# 05_LMS7002M_RF.net
KiCad netlist of a schematic drawn in Altium Designer
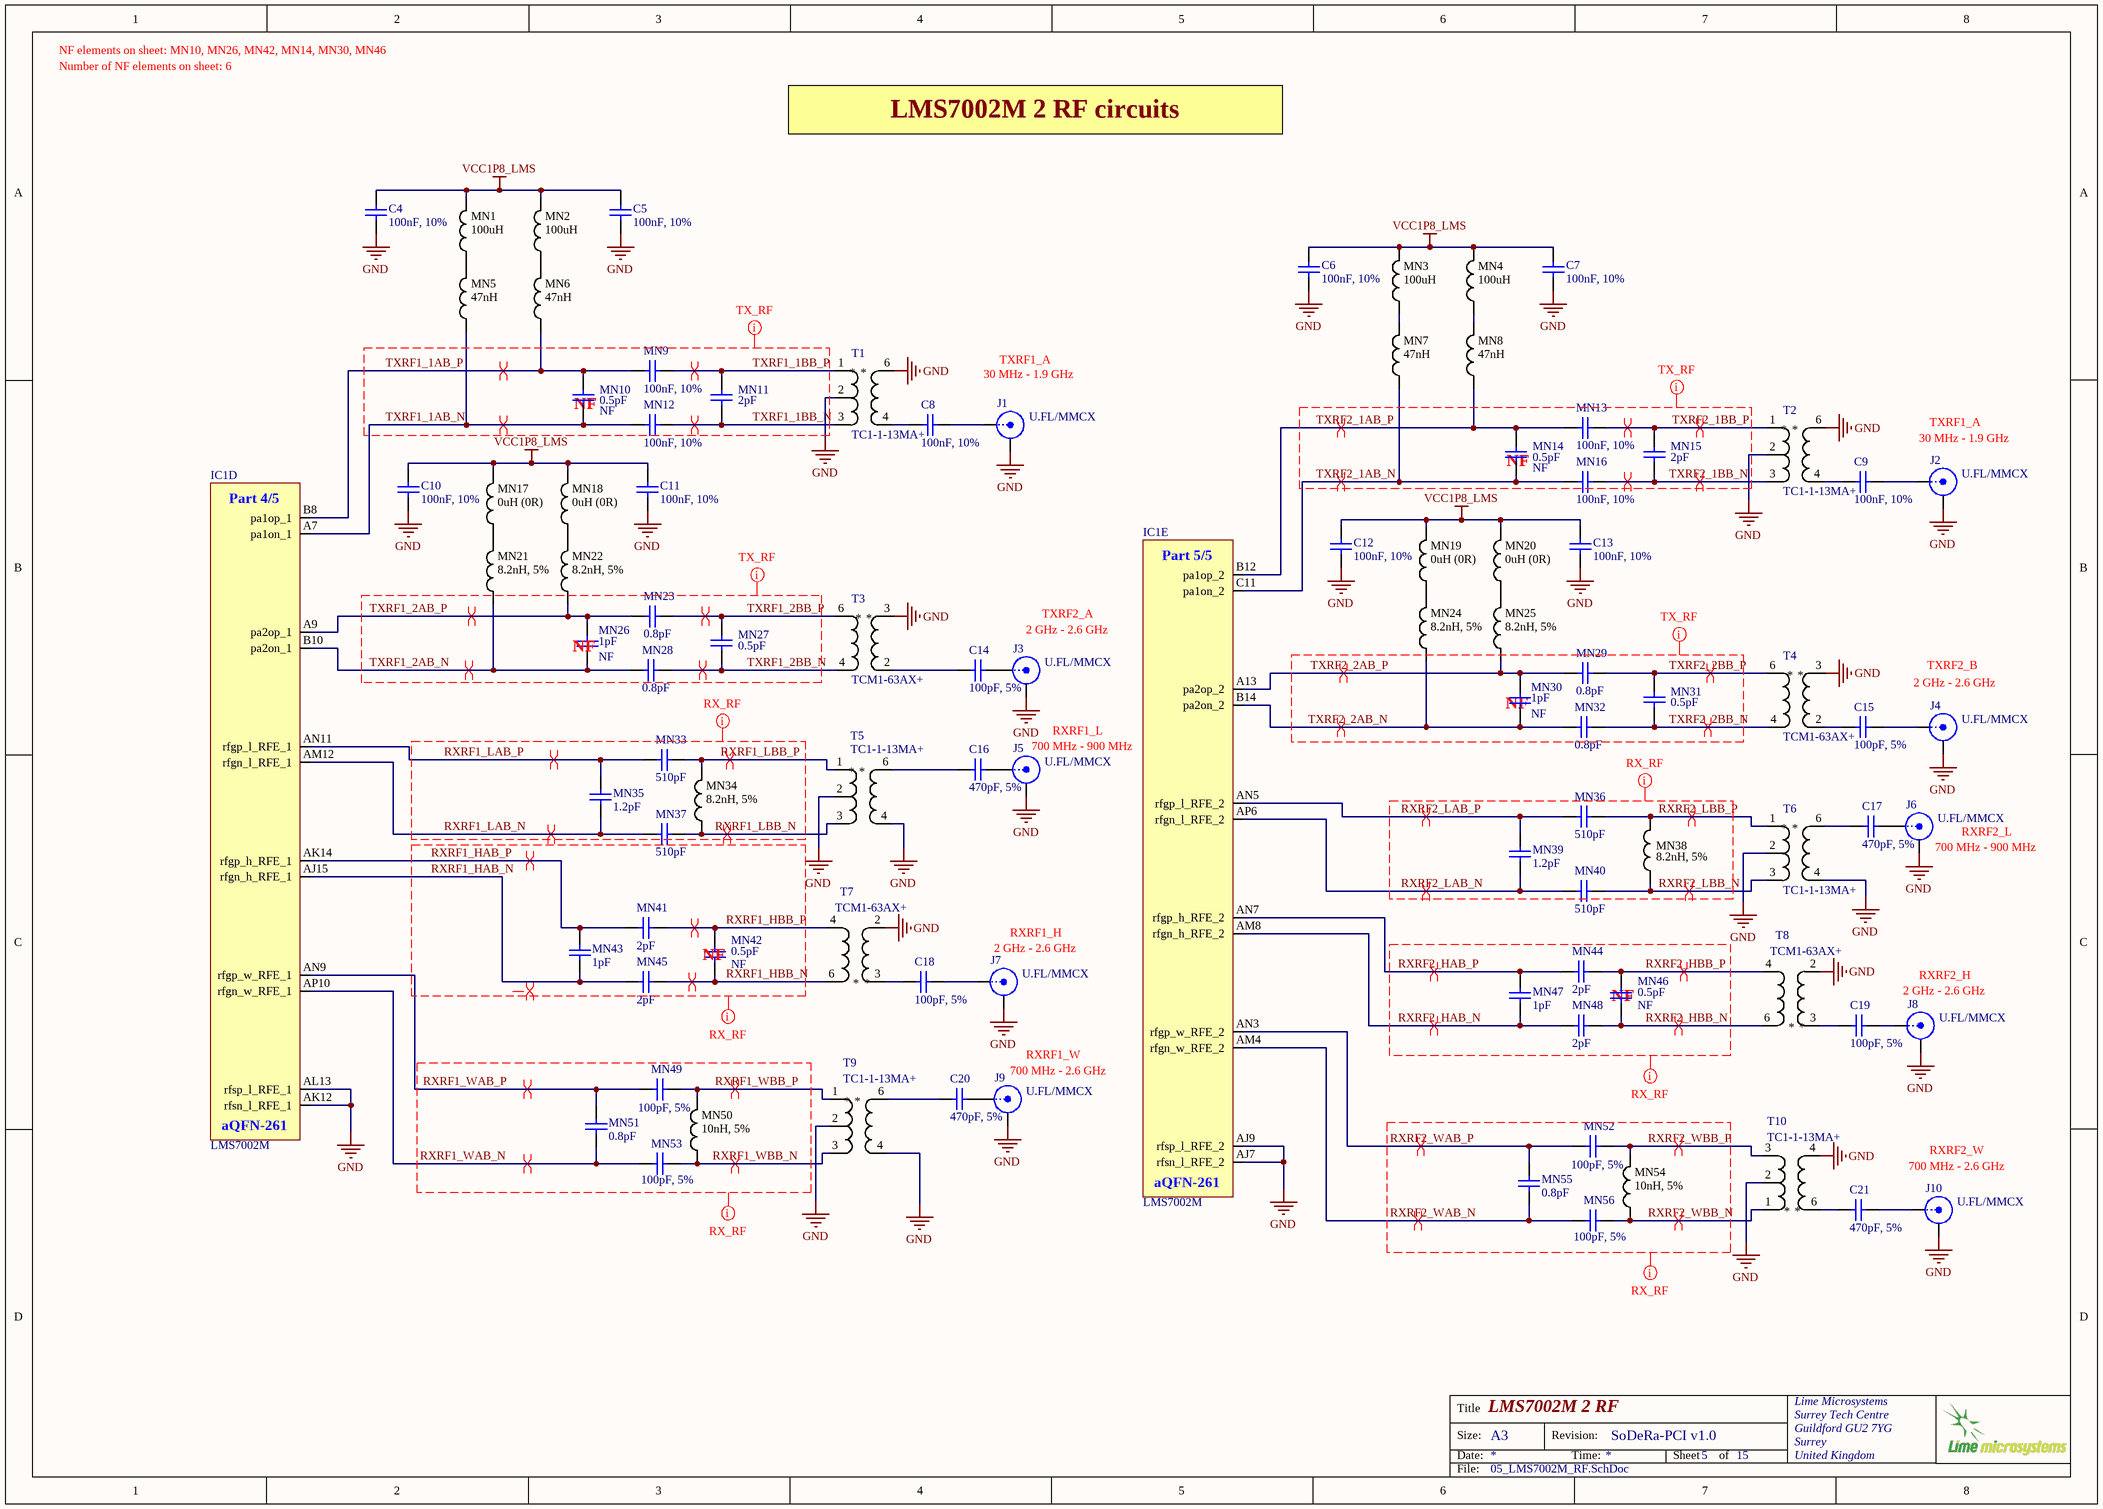
[diagram p0: 05_LMS7002M_RF.SchDoc]

(export (version "E")
  (design (tool "Eeschema 10.0.6"))
  (components
    (comp (ref "C4")
      (value "100nF, 10%")
      (footprint "LimeMicroAltiumLib_pcbLib:CAP0402")
      (fields
        (field (name "MANUFACTURER") "Murata Electronics")
        (field (name "TOLERANCE") "10 %")
        (field (name "MANUFACTURER PART NUMBER") "GRM155R71C104KA88D")
      )
      (libsource (lib "LimeMicroAltiumLib_schLib") (part "Cap_0402"))
    )
    (comp (ref "C5")
      (value "100nF, 10%")
      (footprint "LimeMicroAltiumLib_pcbLib:CAP0402")
      (fields
        (field (name "MANUFACTURER") "Murata Electronics")
        (field (name "TOLERANCE") "10 %")
        (field (name "MANUFACTURER PART NUMBER") "GRM155R71C104KA88D")
      )
      (libsource (lib "LimeMicroAltiumLib_schLib") (part "Cap_0402"))
    )
    (comp (ref "C6")
      (value "100nF, 10%")
      (footprint "LimeMicroAltiumLib_pcbLib:CAP0402")
      (fields
        (field (name "MANUFACTURER") "Murata Electronics")
        (field (name "TOLERANCE") "10 %")
        (field (name "MANUFACTURER PART NUMBER") "GRM155R71C104KA88D")
      )
      (libsource (lib "LimeMicroAltiumLib_schLib") (part "Cap_0402"))
    )
    (comp (ref "C7")
      (value "100nF, 10%")
      (footprint "LimeMicroAltiumLib_pcbLib:CAP0402")
      (fields
        (field (name "MANUFACTURER") "Murata Electronics")
        (field (name "TOLERANCE") "10 %")
        (field (name "MANUFACTURER PART NUMBER") "GRM155R71C104KA88D")
      )
      (libsource (lib "LimeMicroAltiumLib_schLib") (part "Cap_0402"))
    )
    (comp (ref "C8")
      (value "100nF, 10%")
      (footprint "LimeMicroAltiumLib_pcbLib:CAP0402")
      (fields
        (field (name "MANUFACTURER") "Murata Electronics")
        (field (name "TOLERANCE") "10 %")
        (field (name "MANUFACTURER PART NUMBER") "GRM155R71C104KA88D")
      )
      (libsource (lib "LimeMicroAltiumLib_schLib") (part "Cap_0402"))
    )
    (comp (ref "C9")
      (value "100nF, 10%")
      (footprint "LimeMicroAltiumLib_pcbLib:CAP0402")
      (fields
        (field (name "MANUFACTURER") "Murata Electronics")
        (field (name "TOLERANCE") "10 %")
        (field (name "MANUFACTURER PART NUMBER") "GRM155R71C104KA88D")
      )
      (libsource (lib "LimeMicroAltiumLib_schLib") (part "Cap_0402"))
    )
    (comp (ref "C10")
      (value "100nF, 10%")
      (footprint "LimeMicroAltiumLib_pcbLib:CAP0402")
      (fields
        (field (name "MANUFACTURER") "Murata Electronics")
        (field (name "TOLERANCE") "10 %")
        (field (name "MANUFACTURER PART NUMBER") "GRM155R71C104KA88D")
      )
      (libsource (lib "LimeMicroAltiumLib_schLib") (part "Cap_0402"))
    )
    (comp (ref "C11")
      (value "100nF, 10%")
      (footprint "LimeMicroAltiumLib_pcbLib:CAP0402")
      (fields
        (field (name "MANUFACTURER") "Murata Electronics")
        (field (name "TOLERANCE") "10 %")
        (field (name "MANUFACTURER PART NUMBER") "GRM155R71C104KA88D")
      )
      (libsource (lib "LimeMicroAltiumLib_schLib") (part "Cap_0402"))
    )
    (comp (ref "C12")
      (value "100nF, 10%")
      (footprint "LimeMicroAltiumLib_pcbLib:CAP0402")
      (fields
        (field (name "MANUFACTURER") "Murata Electronics")
        (field (name "TOLERANCE") "10 %")
        (field (name "MANUFACTURER PART NUMBER") "GRM155R71C104KA88D")
      )
      (libsource (lib "LimeMicroAltiumLib_schLib") (part "Cap_0402"))
    )
    (comp (ref "C13")
      (value "100nF, 10%")
      (footprint "LimeMicroAltiumLib_pcbLib:CAP0402")
      (fields
        (field (name "MANUFACTURER") "Murata Electronics")
        (field (name "TOLERANCE") "10 %")
        (field (name "MANUFACTURER PART NUMBER") "GRM155R71C104KA88D")
      )
      (libsource (lib "LimeMicroAltiumLib_schLib") (part "Cap_0402"))
    )
    (comp (ref "C14")
      (value "100pF, 5%")
      (footprint "LimeMicroAltiumLib_pcbLib:CAP0402")
      (fields (field (name "TOLERANCE") "±5%") (field (name "MANUFACTURER") "Yageo"))
      (libsource (lib "LimeMicroAltiumLib_schLib") (part "Cap_0402"))
    )
    (comp (ref "C15")
      (value "100pF, 5%")
      (footprint "LimeMicroAltiumLib_pcbLib:CAP0402")
      (fields (field (name "TOLERANCE") "±5%") (field (name "MANUFACTURER") "Yageo"))
      (libsource (lib "LimeMicroAltiumLib_schLib") (part "Cap_0402"))
    )
    (comp (ref "C16")
      (value "470pF, 5%")
      (footprint "LimeMicroAltiumLib_pcbLib:CAP0402")
      (fields
        (field (name "MANUFACTURER PART NUMBER") "C1005C0G1H471J050BA")
        (field (name "TOLERANCE") "±5%")
        (field (name "MANUFACTURER") "TDK Corporation")
      )
      (libsource (lib "LimeMicroAltiumLib_schLib") (part "Cap_0402"))
    )
    (comp (ref "C17")
      (value "470pF, 5%")
      (footprint "LimeMicroAltiumLib_pcbLib:CAP0402")
      (fields
        (field (name "MANUFACTURER PART NUMBER") "C1005C0G1H471J050BA")
        (field (name "TOLERANCE") "±5%")
        (field (name "MANUFACTURER") "TDK Corporation")
      )
      (libsource (lib "LimeMicroAltiumLib_schLib") (part "Cap_0402"))
    )
    (comp (ref "C18")
      (value "100pF, 5%")
      (footprint "LimeMicroAltiumLib_pcbLib:CAP0402")
      (fields (field (name "TOLERANCE") "±5%") (field (name "MANUFACTURER") "Yageo"))
      (libsource (lib "LimeMicroAltiumLib_schLib") (part "Cap_0402"))
    )
    (comp (ref "C19")
      (value "100pF, 5%")
      (footprint "LimeMicroAltiumLib_pcbLib:CAP0402")
      (fields (field (name "TOLERANCE") "±5%") (field (name "MANUFACTURER") "Yageo"))
      (libsource (lib "LimeMicroAltiumLib_schLib") (part "Cap_0402"))
    )
    (comp (ref "C20")
      (value "470pF, 5%")
      (footprint "LimeMicroAltiumLib_pcbLib:CAP0402")
      (fields
        (field (name "MANUFACTURER PART NUMBER") "C1005C0G1H471J050BA")
        (field (name "TOLERANCE") "±5%")
        (field (name "MANUFACTURER") "TDK Corporation")
      )
      (libsource (lib "LimeMicroAltiumLib_schLib") (part "Cap_0402"))
    )
    (comp (ref "C21")
      (value "470pF, 5%")
      (footprint "LimeMicroAltiumLib_pcbLib:CAP0402")
      (fields
        (field (name "MANUFACTURER PART NUMBER") "C1005C0G1H471J050BA")
        (field (name "TOLERANCE") "±5%")
        (field (name "MANUFACTURER") "TDK Corporation")
      )
      (libsource (lib "LimeMicroAltiumLib_schLib") (part "Cap_0402"))
    )
    (comp (ref "IC1")
      (value "LMS7002M")
      (footprint "LimeMicroAltiumLib_pcbLib:LMS7002M")
      (libsource (lib "LimeMicroAltiumLib_schLib") (part "LMS7002M"))
    )
    (comp (ref "J1")
      (value "U.FL/MMCX")
      (footprint "LimeMicroAltiumLib_pcbLib:MMCX_UFL_conn_u")
      (description "CONN UMC RCPT STR 50 OHM SMD")
      (fields (field (name "MANUFACTURER") "Molex, LLC"))
      (libsource (lib "LimeMicroAltiumLib_schLib") (part "RF_IF_connector"))
    )
    (comp (ref "J2")
      (value "U.FL/MMCX")
      (footprint "LimeMicroAltiumLib_pcbLib:MMCX_UFL_conn_u")
      (description "CONN UMC RCPT STR 50 OHM SMD")
      (fields (field (name "MANUFACTURER") "Molex, LLC"))
      (libsource (lib "LimeMicroAltiumLib_schLib") (part "RF_IF_connector"))
    )
    (comp (ref "J3")
      (value "U.FL/MMCX")
      (footprint "LimeMicroAltiumLib_pcbLib:MMCX_UFL_conn_u")
      (description "CONN UMC RCPT STR 50 OHM SMD")
      (fields (field (name "MANUFACTURER") "Molex, LLC"))
      (libsource (lib "LimeMicroAltiumLib_schLib") (part "RF_IF_connector"))
    )
    (comp (ref "J4")
      (value "U.FL/MMCX")
      (footprint "LimeMicroAltiumLib_pcbLib:MMCX_UFL_conn_u")
      (description "CONN UMC RCPT STR 50 OHM SMD")
      (fields (field (name "MANUFACTURER") "Molex, LLC"))
      (libsource (lib "LimeMicroAltiumLib_schLib") (part "RF_IF_connector"))
    )
    (comp (ref "J5")
      (value "U.FL/MMCX")
      (footprint "LimeMicroAltiumLib_pcbLib:MMCX_UFL_conn_u")
      (description "CONN UMC RCPT STR 50 OHM SMD")
      (fields (field (name "MANUFACTURER") "Molex, LLC"))
      (libsource (lib "LimeMicroAltiumLib_schLib") (part "RF_IF_connector"))
    )
    (comp (ref "J6")
      (value "U.FL/MMCX")
      (footprint "LimeMicroAltiumLib_pcbLib:MMCX_UFL_conn_u")
      (description "CONN UMC RCPT STR 50 OHM SMD")
      (fields (field (name "MANUFACTURER") "Molex, LLC"))
      (libsource (lib "LimeMicroAltiumLib_schLib") (part "RF_IF_connector"))
    )
    (comp (ref "J7")
      (value "U.FL/MMCX")
      (footprint "LimeMicroAltiumLib_pcbLib:MMCX_UFL_conn_u")
      (description "CONN UMC RCPT STR 50 OHM SMD")
      (fields (field (name "MANUFACTURER") "Molex, LLC"))
      (libsource (lib "LimeMicroAltiumLib_schLib") (part "RF_IF_connector"))
    )
    (comp (ref "J8")
      (value "U.FL/MMCX")
      (footprint "LimeMicroAltiumLib_pcbLib:MMCX_UFL_conn_u")
      (description "CONN UMC RCPT STR 50 OHM SMD")
      (fields (field (name "MANUFACTURER") "Molex, LLC"))
      (libsource (lib "LimeMicroAltiumLib_schLib") (part "RF_IF_connector"))
    )
    (comp (ref "J9")
      (value "U.FL/MMCX")
      (footprint "LimeMicroAltiumLib_pcbLib:MMCX_UFL_conn_u")
      (description "CONN UMC RCPT STR 50 OHM SMD")
      (fields (field (name "MANUFACTURER") "Molex, LLC"))
      (libsource (lib "LimeMicroAltiumLib_schLib") (part "RF_IF_connector"))
    )
    (comp (ref "J10")
      (value "U.FL/MMCX")
      (footprint "LimeMicroAltiumLib_pcbLib:MMCX_UFL_conn_u")
      (description "CONN UMC RCPT STR 50 OHM SMD")
      (fields (field (name "MANUFACTURER") "Molex, LLC"))
      (libsource (lib "LimeMicroAltiumLib_schLib") (part "RF_IF_connector"))
    )
    (comp (ref "MN1")
      (value "100uH")
      (footprint "LimeMicroAltiumLib_pcbLib:RES0805")
      (fields
        (field (name "TOLERANCE") "±10%")
        (field (name "MANUFACTURER") "TDK Corporation")
        (field (name "MANUFACTURER PART NUMBER") "MLF2012C101KT000")
      )
      (libsource (lib "LimeMicroAltiumLib_schLib") (part "Inductor_0603"))
    )
    (comp (ref "MN2")
      (value "100uH")
      (footprint "LimeMicroAltiumLib_pcbLib:RES0805")
      (fields
        (field (name "TOLERANCE") "±10%")
        (field (name "MANUFACTURER") "TDK Corporation")
        (field (name "MANUFACTURER PART NUMBER") "MLF2012C101KT000")
      )
      (libsource (lib "LimeMicroAltiumLib_schLib") (part "Inductor_0603"))
    )
    (comp (ref "MN3")
      (value "100uH")
      (footprint "LimeMicroAltiumLib_pcbLib:RES0805")
      (fields
        (field (name "TOLERANCE") "±10%")
        (field (name "MANUFACTURER") "TDK Corporation")
        (field (name "MANUFACTURER PART NUMBER") "MLF2012C101KT000")
      )
      (libsource (lib "LimeMicroAltiumLib_schLib") (part "Inductor_0603"))
    )
    (comp (ref "MN4")
      (value "100uH")
      (footprint "LimeMicroAltiumLib_pcbLib:RES0805")
      (fields
        (field (name "TOLERANCE") "±10%")
        (field (name "MANUFACTURER") "TDK Corporation")
        (field (name "MANUFACTURER PART NUMBER") "MLF2012C101KT000")
      )
      (libsource (lib "LimeMicroAltiumLib_schLib") (part "Inductor_0603"))
    )
    (comp (ref "MN5")
      (value "47nH")
      (footprint "LimeMicroAltiumLib_pcbLib:RES0402")
      (fields
        (field (name "MANUFACTURER") "COILCRAFT")
        (field (name "MANUFACTURER PART NUMBER") "0402HP-47NXJLU")
      )
      (libsource (lib "LimeMicroAltiumLib_schLib") (part "Inductor_0603"))
    )
    (comp (ref "MN6")
      (value "47nH")
      (footprint "LimeMicroAltiumLib_pcbLib:RES0402")
      (fields
        (field (name "MANUFACTURER") "COILCRAFT")
        (field (name "MANUFACTURER PART NUMBER") "0402HP-47NXJLU")
      )
      (libsource (lib "LimeMicroAltiumLib_schLib") (part "Inductor_0603"))
    )
    (comp (ref "MN7")
      (value "47nH")
      (footprint "LimeMicroAltiumLib_pcbLib:RES0402")
      (fields
        (field (name "MANUFACTURER") "COILCRAFT")
        (field (name "MANUFACTURER PART NUMBER") "0402HP-47NXJLU")
      )
      (libsource (lib "LimeMicroAltiumLib_schLib") (part "Inductor_0603"))
    )
    (comp (ref "MN8")
      (value "47nH")
      (footprint "LimeMicroAltiumLib_pcbLib:RES0402")
      (fields
        (field (name "MANUFACTURER") "COILCRAFT")
        (field (name "MANUFACTURER PART NUMBER") "0402HP-47NXJLU")
      )
      (libsource (lib "LimeMicroAltiumLib_schLib") (part "Inductor_0603"))
    )
    (comp (ref "MN9")
      (value "100nF, 10%")
      (footprint "LimeMicroAltiumLib_pcbLib:CAP0402")
      (fields
        (field (name "MANUFACTURER") "Murata Electronics")
        (field (name "TOLERANCE") "10 %")
        (field (name "MANUFACTURER PART NUMBER") "GRM155R71C104KA88D")
      )
      (libsource (lib "LimeMicroAltiumLib_schLib") (part "Cap_0402"))
    )
    (comp (ref "MN10")
      (value "0.5pF")
      (footprint "LimeMicroAltiumLib_pcbLib:CAP0402")
      (fields
        (field (name "ASSEMBLY INFO") "NF")
        (field (name "TOLERANCE") "±0.25pF")
        (field (name "MANUFACTURER") "Yageo")
      )
      (libsource (lib "LimeMicroAltiumLib_schLib") (part "Cap_0402"))
    )
    (comp (ref "MN11")
      (value "2pF")
      (footprint "LimeMicroAltiumLib_pcbLib:CAP0402")
      (fields (field (name "MANUFACTURER PART NUMBER") "04025U2R0BAT2A") (field (name "MANUFACTURER") "AVX"))
      (libsource (lib "LimeMicroAltiumLib_schLib") (part "Cap_0402"))
    )
    (comp (ref "MN12")
      (value "100nF, 10%")
      (footprint "LimeMicroAltiumLib_pcbLib:CAP0402")
      (fields
        (field (name "MANUFACTURER") "Murata Electronics")
        (field (name "TOLERANCE") "10 %")
        (field (name "MANUFACTURER PART NUMBER") "GRM155R71C104KA88D")
      )
      (libsource (lib "LimeMicroAltiumLib_schLib") (part "Cap_0402"))
    )
    (comp (ref "MN13")
      (value "100nF, 10%")
      (footprint "LimeMicroAltiumLib_pcbLib:CAP0402")
      (fields
        (field (name "MANUFACTURER") "Murata Electronics")
        (field (name "TOLERANCE") "10 %")
        (field (name "MANUFACTURER PART NUMBER") "GRM155R71C104KA88D")
      )
      (libsource (lib "LimeMicroAltiumLib_schLib") (part "Cap_0402"))
    )
    (comp (ref "MN14")
      (value "0.5pF")
      (footprint "LimeMicroAltiumLib_pcbLib:CAP0402")
      (fields
        (field (name "ASSEMBLY INFO") "NF")
        (field (name "TOLERANCE") "±0.25pF")
        (field (name "MANUFACTURER") "Yageo")
      )
      (libsource (lib "LimeMicroAltiumLib_schLib") (part "Cap_0402"))
    )
    (comp (ref "MN15")
      (value "2pF")
      (footprint "LimeMicroAltiumLib_pcbLib:CAP0402")
      (fields (field (name "MANUFACTURER PART NUMBER") "04025U2R0BAT2A") (field (name "MANUFACTURER") "AVX"))
      (libsource (lib "LimeMicroAltiumLib_schLib") (part "Cap_0402"))
    )
    (comp (ref "MN16")
      (value "100nF, 10%")
      (footprint "LimeMicroAltiumLib_pcbLib:CAP0402")
      (fields
        (field (name "MANUFACTURER") "Murata Electronics")
        (field (name "TOLERANCE") "10 %")
        (field (name "MANUFACTURER PART NUMBER") "GRM155R71C104KA88D")
      )
      (libsource (lib "LimeMicroAltiumLib_schLib") (part "Cap_0402"))
    )
    (comp (ref "MN17")
      (value "0uH (0R)")
      (footprint "LimeMicroAltiumLib_pcbLib:RES0805")
      (fields
        (field (name "MANUFACTURER") "BOURNS")
        (field (name "MANUFACTURER PART NUMBER") "CR0805-J/-000ELF")
      )
      (libsource (lib "LimeMicroAltiumLib_schLib") (part "Inductor_0603"))
    )
    (comp (ref "MN18")
      (value "0uH (0R)")
      (footprint "LimeMicroAltiumLib_pcbLib:RES0805")
      (fields
        (field (name "MANUFACTURER") "BOURNS")
        (field (name "MANUFACTURER PART NUMBER") "CR0805-J/-000ELF")
      )
      (libsource (lib "LimeMicroAltiumLib_schLib") (part "Inductor_0603"))
    )
    (comp (ref "MN19")
      (value "0uH (0R)")
      (footprint "LimeMicroAltiumLib_pcbLib:RES0805")
      (fields
        (field (name "MANUFACTURER") "BOURNS")
        (field (name "MANUFACTURER PART NUMBER") "CR0805-J/-000ELF")
      )
      (libsource (lib "LimeMicroAltiumLib_schLib") (part "Inductor_0603"))
    )
    (comp (ref "MN20")
      (value "0uH (0R)")
      (footprint "LimeMicroAltiumLib_pcbLib:RES0805")
      (fields
        (field (name "MANUFACTURER") "BOURNS")
        (field (name "MANUFACTURER PART NUMBER") "CR0805-J/-000ELF")
      )
      (libsource (lib "LimeMicroAltiumLib_schLib") (part "Inductor_0603"))
    )
    (comp (ref "MN21")
      (value "8.2nH, 5%")
      (footprint "LimeMicroAltiumLib_pcbLib:RES0402")
      (fields (field (name "MANUFACTURER") "COILCRAFT"))
      (libsource (lib "LimeMicroAltiumLib_schLib") (part "Inductor_0603"))
    )
    (comp (ref "MN22")
      (value "8.2nH, 5%")
      (footprint "LimeMicroAltiumLib_pcbLib:RES0402")
      (fields (field (name "MANUFACTURER") "COILCRAFT"))
      (libsource (lib "LimeMicroAltiumLib_schLib") (part "Inductor_0603"))
    )
    (comp (ref "MN23")
      (value "0.8pF")
      (footprint "LimeMicroAltiumLib_pcbLib:CAP0402")
      (fields
        (field (name "TOLERANCE") "±0.1pF")
        (field (name "MANUFACTURER") "Murata Electronics North America")
        (field (name "MANUFACTURER PART NUMBER") "GRM1555C1HR80BA01D")
      )
      (libsource (lib "LimeMicroAltiumLib_schLib") (part "Cap_0402"))
    )
    (comp (ref "MN24")
      (value "8.2nH, 5%")
      (footprint "LimeMicroAltiumLib_pcbLib:RES0402")
      (fields (field (name "MANUFACTURER") "COILCRAFT"))
      (libsource (lib "LimeMicroAltiumLib_schLib") (part "Inductor_0603"))
    )
    (comp (ref "MN25")
      (value "8.2nH, 5%")
      (footprint "LimeMicroAltiumLib_pcbLib:RES0402")
      (fields (field (name "MANUFACTURER") "COILCRAFT"))
      (libsource (lib "LimeMicroAltiumLib_schLib") (part "Inductor_0603"))
    )
    (comp (ref "MN26")
      (value "1pF")
      (footprint "LimeMicroAltiumLib_pcbLib:CAP0402")
      (fields
        (field (name "ASSEMBLY INFO") "NF")
        (field (name "MANUFACTURER") "TDK Corporation")
        (field (name "TOLERANCE") "±0.1pF")
      )
      (libsource (lib "LimeMicroAltiumLib_schLib") (part "Cap_0402"))
    )
    (comp (ref "MN27")
      (value "0.5pF")
      (footprint "LimeMicroAltiumLib_pcbLib:CAP0402")
      (fields (field (name "TOLERANCE") "±0.25pF") (field (name "MANUFACTURER") "Yageo"))
      (libsource (lib "LimeMicroAltiumLib_schLib") (part "Cap_0402"))
    )
    (comp (ref "MN28")
      (value "0.8pF")
      (footprint "LimeMicroAltiumLib_pcbLib:CAP0402")
      (fields
        (field (name "TOLERANCE") "±0.1pF")
        (field (name "MANUFACTURER") "Murata Electronics North America")
        (field (name "MANUFACTURER PART NUMBER") "GRM1555C1HR80BA01D")
      )
      (libsource (lib "LimeMicroAltiumLib_schLib") (part "Cap_0402"))
    )
    (comp (ref "MN29")
      (value "0.8pF")
      (footprint "LimeMicroAltiumLib_pcbLib:CAP0402")
      (fields
        (field (name "TOLERANCE") "±0.1pF")
        (field (name "MANUFACTURER") "Murata Electronics North America")
        (field (name "MANUFACTURER PART NUMBER") "GRM1555C1HR80BA01D")
      )
      (libsource (lib "LimeMicroAltiumLib_schLib") (part "Cap_0402"))
    )
    (comp (ref "MN30")
      (value "1pF")
      (footprint "LimeMicroAltiumLib_pcbLib:CAP0402")
      (fields
        (field (name "ASSEMBLY INFO") "NF")
        (field (name "MANUFACTURER") "TDK Corporation")
        (field (name "TOLERANCE") "±0.1pF")
      )
      (libsource (lib "LimeMicroAltiumLib_schLib") (part "Cap_0402"))
    )
    (comp (ref "MN31")
      (value "0.5pF")
      (footprint "LimeMicroAltiumLib_pcbLib:CAP0402")
      (fields (field (name "TOLERANCE") "±0.25pF") (field (name "MANUFACTURER") "Yageo"))
      (libsource (lib "LimeMicroAltiumLib_schLib") (part "Cap_0402"))
    )
    (comp (ref "MN32")
      (value "0.8pF")
      (footprint "LimeMicroAltiumLib_pcbLib:CAP0402")
      (fields
        (field (name "TOLERANCE") "±0.1pF")
        (field (name "MANUFACTURER") "Murata Electronics North America")
        (field (name "MANUFACTURER PART NUMBER") "GRM1555C1HR80BA01D")
      )
      (libsource (lib "LimeMicroAltiumLib_schLib") (part "Cap_0402"))
    )
    (comp (ref "MN33")
      (value "510pF")
      (footprint "LimeMicroAltiumLib_pcbLib:CAP0402")
      (fields
        (field (name "TOLERANCE") "±5%")
        (field (name "MANUFACTURER") "Murata Electronics North America")
        (field (name "MANUFACTURER PART NUMBER") "GRM1555C1H511JA01D")
      )
      (libsource (lib "LimeMicroAltiumLib_schLib") (part "Cap_0402"))
    )
    (comp (ref "MN34")
      (value "8.2nH, 5%")
      (footprint "LimeMicroAltiumLib_pcbLib:RES0402")
      (fields (field (name "MANUFACTURER") "COILCRAFT"))
      (libsource (lib "LimeMicroAltiumLib_schLib") (part "Inductor_0603"))
    )
    (comp (ref "MN35")
      (value "1.2pF")
      (footprint "LimeMicroAltiumLib_pcbLib:CAP0402")
      (fields
        (field (name "MANUFACTURER") "Murata Electronics North America")
        (field (name "MANUFACTURER PART NUMBER") "GRM1555C1H1R2CA01D")
        (field (name "TOLERANCE") "±0.25pF")
      )
      (libsource (lib "LimeMicroAltiumLib_schLib") (part "Cap_0402"))
    )
    (comp (ref "MN36")
      (value "510pF")
      (footprint "LimeMicroAltiumLib_pcbLib:CAP0402")
      (fields
        (field (name "TOLERANCE") "±5%")
        (field (name "MANUFACTURER") "Murata Electronics North America")
        (field (name "MANUFACTURER PART NUMBER") "GRM1555C1H511JA01D")
      )
      (libsource (lib "LimeMicroAltiumLib_schLib") (part "Cap_0402"))
    )
    (comp (ref "MN37")
      (value "510pF")
      (footprint "LimeMicroAltiumLib_pcbLib:CAP0402")
      (fields
        (field (name "TOLERANCE") "±5%")
        (field (name "MANUFACTURER") "Murata Electronics North America")
        (field (name "MANUFACTURER PART NUMBER") "GRM1555C1H511JA01D")
      )
      (libsource (lib "LimeMicroAltiumLib_schLib") (part "Cap_0402"))
    )
    (comp (ref "MN38")
      (value "8.2nH, 5%")
      (footprint "LimeMicroAltiumLib_pcbLib:RES0402")
      (fields (field (name "MANUFACTURER") "COILCRAFT"))
      (libsource (lib "LimeMicroAltiumLib_schLib") (part "Inductor_0603"))
    )
    (comp (ref "MN39")
      (value "1.2pF")
      (footprint "LimeMicroAltiumLib_pcbLib:CAP0402")
      (fields
        (field (name "MANUFACTURER") "Murata Electronics North America")
        (field (name "MANUFACTURER PART NUMBER") "GRM1555C1H1R2CA01D")
        (field (name "TOLERANCE") "±0.25pF")
      )
      (libsource (lib "LimeMicroAltiumLib_schLib") (part "Cap_0402"))
    )
    (comp (ref "MN40")
      (value "510pF")
      (footprint "LimeMicroAltiumLib_pcbLib:CAP0402")
      (fields
        (field (name "TOLERANCE") "±5%")
        (field (name "MANUFACTURER") "Murata Electronics North America")
        (field (name "MANUFACTURER PART NUMBER") "GRM1555C1H511JA01D")
      )
      (libsource (lib "LimeMicroAltiumLib_schLib") (part "Cap_0402"))
    )
    (comp (ref "MN41")
      (value "2pF")
      (footprint "LimeMicroAltiumLib_pcbLib:CAP0402")
      (fields (field (name "MANUFACTURER PART NUMBER") "04025U2R0BAT2A") (field (name "MANUFACTURER") "AVX"))
      (libsource (lib "LimeMicroAltiumLib_schLib") (part "Cap_0402"))
    )
    (comp (ref "MN42")
      (value "0.5pF")
      (footprint "LimeMicroAltiumLib_pcbLib:CAP0402")
      (fields
        (field (name "ASSEMBLY INFO") "NF")
        (field (name "TOLERANCE") "±0.25pF")
        (field (name "MANUFACTURER") "Yageo")
      )
      (libsource (lib "LimeMicroAltiumLib_schLib") (part "Cap_0402"))
    )
    (comp (ref "MN43")
      (value "1pF")
      (footprint "LimeMicroAltiumLib_pcbLib:CAP0402")
      (fields (field (name "MANUFACTURER") "TDK Corporation") (field (name "TOLERANCE") "±0.1pF"))
      (libsource (lib "LimeMicroAltiumLib_schLib") (part "Cap_0402"))
    )
    (comp (ref "MN44")
      (value "2pF")
      (footprint "LimeMicroAltiumLib_pcbLib:CAP0402")
      (fields (field (name "MANUFACTURER PART NUMBER") "04025U2R0BAT2A") (field (name "MANUFACTURER") "AVX"))
      (libsource (lib "LimeMicroAltiumLib_schLib") (part "Cap_0402"))
    )
    (comp (ref "MN45")
      (value "2pF")
      (footprint "LimeMicroAltiumLib_pcbLib:CAP0402")
      (fields (field (name "MANUFACTURER PART NUMBER") "04025U2R0BAT2A") (field (name "MANUFACTURER") "AVX"))
      (libsource (lib "LimeMicroAltiumLib_schLib") (part "Cap_0402"))
    )
    (comp (ref "MN46")
      (value "0.5pF")
      (footprint "LimeMicroAltiumLib_pcbLib:CAP0402")
      (fields
        (field (name "ASSEMBLY INFO") "NF")
        (field (name "TOLERANCE") "±0.25pF")
        (field (name "MANUFACTURER") "Yageo")
      )
      (libsource (lib "LimeMicroAltiumLib_schLib") (part "Cap_0402"))
    )
    (comp (ref "MN47")
      (value "1pF")
      (footprint "LimeMicroAltiumLib_pcbLib:CAP0402")
      (fields (field (name "MANUFACTURER") "TDK Corporation") (field (name "TOLERANCE") "±0.1pF"))
      (libsource (lib "LimeMicroAltiumLib_schLib") (part "Cap_0402"))
    )
    (comp (ref "MN48")
      (value "2pF")
      (footprint "LimeMicroAltiumLib_pcbLib:CAP0402")
      (fields (field (name "MANUFACTURER PART NUMBER") "04025U2R0BAT2A") (field (name "MANUFACTURER") "AVX"))
      (libsource (lib "LimeMicroAltiumLib_schLib") (part "Cap_0402"))
    )
    (comp (ref "MN49")
      (value "100pF, 5%")
      (footprint "LimeMicroAltiumLib_pcbLib:CAP0402")
      (fields (field (name "TOLERANCE") "±5%") (field (name "MANUFACTURER") "Yageo"))
      (libsource (lib "LimeMicroAltiumLib_schLib") (part "Cap_0402"))
    )
    (comp (ref "MN50")
      (value "10nH, 5%")
      (footprint "LimeMicroAltiumLib_pcbLib:RES0402")
      (fields
        (field (name "MANUFACTURER PART NUMBER") "0402HP-10NXJLU")
        (field (name "MANUFACTURER") "COILCRAFT")
      )
      (libsource (lib "LimeMicroAltiumLib_schLib") (part "Inductor_0603"))
    )
    (comp (ref "MN51")
      (value "0.8pF")
      (footprint "LimeMicroAltiumLib_pcbLib:CAP0402")
      (fields
        (field (name "TOLERANCE") "±0.1pF")
        (field (name "MANUFACTURER") "Murata Electronics North America")
        (field (name "MANUFACTURER PART NUMBER") "GRM1555C1HR80BA01D")
      )
      (libsource (lib "LimeMicroAltiumLib_schLib") (part "Cap_0402"))
    )
    (comp (ref "MN52")
      (value "100pF, 5%")
      (footprint "LimeMicroAltiumLib_pcbLib:CAP0402")
      (fields (field (name "TOLERANCE") "±5%") (field (name "MANUFACTURER") "Yageo"))
      (libsource (lib "LimeMicroAltiumLib_schLib") (part "Cap_0402"))
    )
    (comp (ref "MN53")
      (value "100pF, 5%")
      (footprint "LimeMicroAltiumLib_pcbLib:CAP0402")
      (fields (field (name "TOLERANCE") "±5%") (field (name "MANUFACTURER") "Yageo"))
      (libsource (lib "LimeMicroAltiumLib_schLib") (part "Cap_0402"))
    )
    (comp (ref "MN54")
      (value "10nH, 5%")
      (footprint "LimeMicroAltiumLib_pcbLib:RES0402")
      (fields
        (field (name "MANUFACTURER PART NUMBER") "0402HP-10NXJLU")
        (field (name "MANUFACTURER") "COILCRAFT")
      )
      (libsource (lib "LimeMicroAltiumLib_schLib") (part "Inductor_0603"))
    )
    (comp (ref "MN55")
      (value "0.8pF")
      (footprint "LimeMicroAltiumLib_pcbLib:CAP0402")
      (fields
        (field (name "TOLERANCE") "±0.1pF")
        (field (name "MANUFACTURER") "Murata Electronics North America")
        (field (name "MANUFACTURER PART NUMBER") "GRM1555C1HR80BA01D")
      )
      (libsource (lib "LimeMicroAltiumLib_schLib") (part "Cap_0402"))
    )
    (comp (ref "MN56")
      (value "100pF, 5%")
      (footprint "LimeMicroAltiumLib_pcbLib:CAP0402")
      (fields (field (name "TOLERANCE") "±5%") (field (name "MANUFACTURER") "Yageo"))
      (libsource (lib "LimeMicroAltiumLib_schLib") (part "Cap_0402"))
    )
    (comp (ref "T1")
      (value "TC1-1-13MA+")
      (footprint "LimeMicroAltiumLib_pcbLib:TC1-1-13MA+_v2")
      (fields (field (name "MANUFACTURER") "Mini-Circuits"))
      (libsource (lib "LimeMicroAltiumLib_schLib") (part "Balun"))
    )
    (comp (ref "T2")
      (value "TC1-1-13MA+")
      (footprint "LimeMicroAltiumLib_pcbLib:TC1-1-13MA+_v2")
      (fields (field (name "MANUFACTURER") "Mini-Circuits"))
      (libsource (lib "LimeMicroAltiumLib_schLib") (part "Balun"))
    )
    (comp (ref "T3")
      (value "TCM1-63AX+")
      (footprint "LimeMicroAltiumLib_pcbLib:TCM1-63AX+_v2")
      (fields (field (name "MANUFACTURER") "Mini-circuits"))
      (libsource (lib "LimeMicroAltiumLib_schLib") (part "Balun_v2"))
    )
    (comp (ref "T4")
      (value "TCM1-63AX+")
      (footprint "LimeMicroAltiumLib_pcbLib:TCM1-63AX+_v2")
      (fields (field (name "MANUFACTURER") "Mini-circuits"))
      (libsource (lib "LimeMicroAltiumLib_schLib") (part "Balun_v2"))
    )
    (comp (ref "T5")
      (value "TC1-1-13MA+")
      (footprint "LimeMicroAltiumLib_pcbLib:TC1-1-13MA+_v2")
      (fields (field (name "MANUFACTURER") "Mini-Circuits"))
      (libsource (lib "LimeMicroAltiumLib_schLib") (part "Balun"))
    )
    (comp (ref "T6")
      (value "TC1-1-13MA+")
      (footprint "LimeMicroAltiumLib_pcbLib:TC1-1-13MA+_v2")
      (fields (field (name "MANUFACTURER") "Mini-Circuits"))
      (libsource (lib "LimeMicroAltiumLib_schLib") (part "Balun"))
    )
    (comp (ref "T7")
      (value "TCM1-63AX+")
      (footprint "LimeMicroAltiumLib_pcbLib:TCM1-63AX+_v2")
      (fields (field (name "MANUFACTURER") "Mini-circuits"))
      (libsource (lib "") (part "Balun_v2_1"))
    )
    (comp (ref "T8")
      (value "TCM1-63AX+")
      (footprint "LimeMicroAltiumLib_pcbLib:TCM1-63AX+_v2")
      (fields (field (name "MANUFACTURER") "Mini-circuits"))
      (libsource (lib "") (part "Balun_v2_1"))
    )
    (comp (ref "T9")
      (value "TC1-1-13MA+")
      (footprint "LimeMicroAltiumLib_pcbLib:TC1-1-13MA+_v2")
      (fields (field (name "MANUFACTURER") "Mini-Circuits"))
      (libsource (lib "LimeMicroAltiumLib_schLib") (part "Balun"))
    )
    (comp (ref "T10")
      (value "TC1-1-13MA+")
      (footprint "LimeMicroAltiumLib_pcbLib:TC1-1-13MA+_v2")
      (fields (field (name "MANUFACTURER") "Mini-Circuits"))
      (libsource (lib "") (part "Balun_1"))
    )
  )
  (nets
    (net (code "1") (name "/RXRF1_HAB_N") (class "Default")
      (node (ref "IC1") (pin "AJ15") (pinfunction "rfgn_h_RFE_1_AJ15") (pintype "passive"))
      (node (ref "MN43") (pin "1") (pinfunction "1_1") (pintype "passive"))
      (node (ref "MN45") (pin "2") (pinfunction "2_2") (pintype "passive"))
    )
    (net (code "2") (name "/RXRF1_HAB_P") (class "Default")
      (node (ref "IC1") (pin "AK14") (pinfunction "rfgp_h_RFE_1_AK14") (pintype "passive"))
      (node (ref "MN41") (pin "2") (pinfunction "2_2") (pintype "passive"))
      (node (ref "MN43") (pin "2") (pinfunction "2_2") (pintype "passive"))
    )
    (net (code "3") (name "/RXRF1_HBB_N") (class "Default")
      (node (ref "MN42") (pin "1") (pinfunction "1_1") (pintype "passive"))
      (node (ref "MN45") (pin "1") (pinfunction "1_1") (pintype "passive"))
      (node (ref "T7") (pin "6") (pinfunction "6_6") (pintype "passive"))
    )
    (net (code "4") (name "/RXRF1_HBB_P") (class "Default")
      (node (ref "MN41") (pin "1") (pinfunction "1_1") (pintype "passive"))
      (node (ref "MN42") (pin "2") (pinfunction "2_2") (pintype "passive"))
      (node (ref "T7") (pin "4") (pinfunction "4_4") (pintype "passive"))
    )
    (net (code "5") (name "/RXRF1_LAB_N") (class "Default")
      (node (ref "IC1") (pin "AM12") (pinfunction "rfgn_l_RFE_1_AM12") (pintype "passive"))
      (node (ref "MN35") (pin "1") (pinfunction "1_1") (pintype "passive"))
      (node (ref "MN37") (pin "2") (pinfunction "2_2") (pintype "passive"))
    )
    (net (code "6") (name "/RXRF1_LAB_P") (class "Default")
      (node (ref "IC1") (pin "AN11") (pinfunction "rfgp_l_RFE_1_AN11") (pintype "passive"))
      (node (ref "MN33") (pin "2") (pinfunction "2_2") (pintype "passive"))
      (node (ref "MN35") (pin "2") (pinfunction "2_2") (pintype "passive"))
    )
    (net (code "7") (name "/RXRF1_LBB_N") (class "Default")
      (node (ref "MN34") (pin "1") (pinfunction "1_1") (pintype "passive"))
      (node (ref "MN37") (pin "1") (pinfunction "1_1") (pintype "passive"))
      (node (ref "T5") (pin "3") (pinfunction "3_3") (pintype "passive"))
    )
    (net (code "8") (name "/RXRF1_LBB_P") (class "Default")
      (node (ref "MN33") (pin "1") (pinfunction "1_1") (pintype "passive"))
      (node (ref "MN34") (pin "2") (pinfunction "2_2") (pintype "passive"))
      (node (ref "T5") (pin "1") (pinfunction "1_1") (pintype "passive"))
    )
    (net (code "9") (name "/RXRF1_WAB_N") (class "Default")
      (node (ref "IC1") (pin "AP10") (pinfunction "rfgn_w_RFE_1_AP10") (pintype "passive"))
      (node (ref "MN51") (pin "2") (pinfunction "2_2") (pintype "passive"))
      (node (ref "MN53") (pin "2") (pinfunction "2_2") (pintype "passive"))
    )
    (net (code "10") (name "/RXRF1_WAB_P") (class "Default")
      (node (ref "IC1") (pin "AN9") (pinfunction "rfgp_w_RFE_1_AN9") (pintype "passive"))
      (node (ref "MN49") (pin "2") (pinfunction "2_2") (pintype "passive"))
      (node (ref "MN51") (pin "1") (pinfunction "1_1") (pintype "passive"))
    )
    (net (code "11") (name "/RXRF1_WBB_N") (class "Default")
      (node (ref "MN50") (pin "1") (pinfunction "1_1") (pintype "passive"))
      (node (ref "MN53") (pin "1") (pinfunction "1_1") (pintype "passive"))
      (node (ref "T9") (pin "3") (pinfunction "3_3") (pintype "passive"))
    )
    (net (code "12") (name "/RXRF1_WBB_P") (class "Default")
      (node (ref "MN49") (pin "1") (pinfunction "1_1") (pintype "passive"))
      (node (ref "MN50") (pin "2") (pinfunction "2_2") (pintype "passive"))
      (node (ref "T9") (pin "1") (pinfunction "1_1") (pintype "passive"))
    )
    (net (code "13") (name "/RXRF2_HAB_N") (class "Default")
      (node (ref "IC1") (pin "AM8") (pinfunction "rfgn_h_RFE_2_AM8") (pintype "passive"))
      (node (ref "MN47") (pin "1") (pinfunction "1_1") (pintype "passive"))
      (node (ref "MN48") (pin "2") (pinfunction "2_2") (pintype "passive"))
    )
    (net (code "14") (name "/RXRF2_HAB_P") (class "Default")
      (node (ref "IC1") (pin "AN7") (pinfunction "rfgp_h_RFE_2_AN7") (pintype "passive"))
      (node (ref "MN44") (pin "2") (pinfunction "2_2") (pintype "passive"))
      (node (ref "MN47") (pin "2") (pinfunction "2_2") (pintype "passive"))
    )
    (net (code "15") (name "/RXRF2_HBB_N") (class "Default")
      (node (ref "MN46") (pin "1") (pinfunction "1_1") (pintype "passive"))
      (node (ref "MN48") (pin "1") (pinfunction "1_1") (pintype "passive"))
      (node (ref "T8") (pin "6") (pinfunction "6_6") (pintype "passive"))
    )
    (net (code "16") (name "/RXRF2_HBB_P") (class "Default")
      (node (ref "MN44") (pin "1") (pinfunction "1_1") (pintype "passive"))
      (node (ref "MN46") (pin "2") (pinfunction "2_2") (pintype "passive"))
      (node (ref "T8") (pin "4") (pinfunction "4_4") (pintype "passive"))
    )
    (net (code "17") (name "/RXRF2_LAB_N") (class "Default")
      (node (ref "IC1") (pin "AP6") (pinfunction "rfgn_l_RFE_2_AP6") (pintype "passive"))
      (node (ref "MN39") (pin "1") (pinfunction "1_1") (pintype "passive"))
      (node (ref "MN40") (pin "2") (pinfunction "2_2") (pintype "passive"))
    )
    (net (code "18") (name "/RXRF2_LAB_P") (class "Default")
      (node (ref "IC1") (pin "AN5") (pinfunction "rfgp_l_RFE_2_AN5") (pintype "passive"))
      (node (ref "MN36") (pin "2") (pinfunction "2_2") (pintype "passive"))
      (node (ref "MN39") (pin "2") (pinfunction "2_2") (pintype "passive"))
    )
    (net (code "19") (name "/RXRF2_LBB_N") (class "Default")
      (node (ref "MN38") (pin "1") (pinfunction "1_1") (pintype "passive"))
      (node (ref "MN40") (pin "1") (pinfunction "1_1") (pintype "passive"))
      (node (ref "T6") (pin "3") (pinfunction "3_3") (pintype "passive"))
    )
    (net (code "20") (name "/RXRF2_LBB_P") (class "Default")
      (node (ref "MN36") (pin "1") (pinfunction "1_1") (pintype "passive"))
      (node (ref "MN38") (pin "2") (pinfunction "2_2") (pintype "passive"))
      (node (ref "T6") (pin "1") (pinfunction "1_1") (pintype "passive"))
    )
    (net (code "21") (name "/RXRF2_WAB_N") (class "Default")
      (node (ref "IC1") (pin "AM4") (pinfunction "rfgn_w_RFE_2_AM4") (pintype "passive"))
      (node (ref "MN55") (pin "2") (pinfunction "2_2") (pintype "passive"))
      (node (ref "MN56") (pin "2") (pinfunction "2_2") (pintype "passive"))
    )
    (net (code "22") (name "/RXRF2_WAB_P") (class "Default")
      (node (ref "IC1") (pin "AN3") (pinfunction "rfgp_w_RFE_2_AN3") (pintype "passive"))
      (node (ref "MN52") (pin "2") (pinfunction "2_2") (pintype "passive"))
      (node (ref "MN55") (pin "1") (pinfunction "1_1") (pintype "passive"))
    )
    (net (code "23") (name "/RXRF2_WBB_N") (class "Default")
      (node (ref "MN54") (pin "1") (pinfunction "1_1") (pintype "passive"))
      (node (ref "MN56") (pin "1") (pinfunction "1_1") (pintype "passive"))
      (node (ref "T10") (pin "1") (pinfunction "1_1") (pintype "passive"))
    )
    (net (code "24") (name "/RXRF2_WBB_P") (class "Default")
      (node (ref "MN52") (pin "1") (pinfunction "1_1") (pintype "passive"))
      (node (ref "MN54") (pin "2") (pinfunction "2_2") (pintype "passive"))
      (node (ref "T10") (pin "3") (pinfunction "3_3") (pintype "passive"))
    )
    (net (code "25") (name "/TXRF1_1AB_N") (class "Default")
      (node (ref "IC1") (pin "A7") (pinfunction "pa1on_1_A7") (pintype "passive"))
      (node (ref "MN10") (pin "1") (pinfunction "1_1") (pintype "passive"))
      (node (ref "MN12") (pin "1") (pinfunction "1_1") (pintype "passive"))
      (node (ref "MN5") (pin "1") (pinfunction "1_1") (pintype "passive"))
    )
    (net (code "26") (name "/TXRF1_1AB_P") (class "Default")
      (node (ref "IC1") (pin "B8") (pinfunction "pa1op_1_B8") (pintype "passive"))
      (node (ref "MN10") (pin "2") (pinfunction "2_2") (pintype "passive"))
      (node (ref "MN6") (pin "1") (pinfunction "1_1") (pintype "passive"))
      (node (ref "MN9") (pin "2") (pinfunction "2_2") (pintype "passive"))
    )
    (net (code "27") (name "/TXRF1_1BB_N") (class "Default")
      (node (ref "MN11") (pin "1") (pinfunction "1_1") (pintype "passive"))
      (node (ref "MN12") (pin "2") (pinfunction "2_2") (pintype "passive"))
      (node (ref "T1") (pin "3") (pinfunction "3_3") (pintype "passive"))
    )
    (net (code "28") (name "/TXRF1_1BB_P") (class "Default")
      (node (ref "MN11") (pin "2") (pinfunction "2_2") (pintype "passive"))
      (node (ref "MN9") (pin "1") (pinfunction "1_1") (pintype "passive"))
      (node (ref "T1") (pin "1") (pinfunction "1_1") (pintype "passive"))
    )
    (net (code "29") (name "/TXRF1_2AB_N") (class "Default")
      (node (ref "IC1") (pin "B10") (pinfunction "pa2on_1_B10") (pintype "passive"))
      (node (ref "MN21") (pin "1") (pinfunction "1_1") (pintype "passive"))
      (node (ref "MN26") (pin "2") (pinfunction "2_2") (pintype "passive"))
      (node (ref "MN28") (pin "2") (pinfunction "2_2") (pintype "passive"))
    )
    (net (code "30") (name "/TXRF1_2AB_P") (class "Default")
      (node (ref "IC1") (pin "A9") (pinfunction "pa2op_1_A9") (pintype "passive"))
      (node (ref "MN22") (pin "1") (pinfunction "1_1") (pintype "passive"))
      (node (ref "MN23") (pin "2") (pinfunction "2_2") (pintype "passive"))
      (node (ref "MN26") (pin "1") (pinfunction "1_1") (pintype "passive"))
    )
    (net (code "31") (name "/TXRF1_2BB_N") (class "Default")
      (node (ref "MN27") (pin "1") (pinfunction "1_1") (pintype "passive"))
      (node (ref "MN28") (pin "1") (pinfunction "1_1") (pintype "passive"))
      (node (ref "T3") (pin "4") (pinfunction "4_4") (pintype "passive"))
    )
    (net (code "32") (name "/TXRF1_2BB_P") (class "Default")
      (node (ref "MN23") (pin "1") (pinfunction "1_1") (pintype "passive"))
      (node (ref "MN27") (pin "2") (pinfunction "2_2") (pintype "passive"))
      (node (ref "T3") (pin "6") (pinfunction "6_6") (pintype "passive"))
    )
    (net (code "33") (name "/TXRF2_1AB_N") (class "Default")
      (node (ref "IC1") (pin "C11") (pinfunction "pa1on_2_C11") (pintype "passive"))
      (node (ref "MN14") (pin "1") (pinfunction "1_1") (pintype "passive"))
      (node (ref "MN16") (pin "1") (pinfunction "1_1") (pintype "passive"))
      (node (ref "MN7") (pin "1") (pinfunction "1_1") (pintype "passive"))
    )
    (net (code "34") (name "/TXRF2_1AB_P") (class "Default")
      (node (ref "IC1") (pin "B12") (pinfunction "pa1op_2_B12") (pintype "passive"))
      (node (ref "MN13") (pin "2") (pinfunction "2_2") (pintype "passive"))
      (node (ref "MN14") (pin "2") (pinfunction "2_2") (pintype "passive"))
      (node (ref "MN8") (pin "1") (pinfunction "1_1") (pintype "passive"))
    )
    (net (code "35") (name "/TXRF2_1BB_N") (class "Default")
      (node (ref "MN15") (pin "1") (pinfunction "1_1") (pintype "passive"))
      (node (ref "MN16") (pin "2") (pinfunction "2_2") (pintype "passive"))
      (node (ref "T2") (pin "3") (pinfunction "3_3") (pintype "passive"))
    )
    (net (code "36") (name "/TXRF2_1BB_P") (class "Default")
      (node (ref "MN13") (pin "1") (pinfunction "1_1") (pintype "passive"))
      (node (ref "MN15") (pin "2") (pinfunction "2_2") (pintype "passive"))
      (node (ref "T2") (pin "1") (pinfunction "1_1") (pintype "passive"))
    )
    (net (code "37") (name "/TXRF2_2AB_N") (class "Default")
      (node (ref "IC1") (pin "B14") (pinfunction "pa2on_2_B14") (pintype "passive"))
      (node (ref "MN24") (pin "1") (pinfunction "1_1") (pintype "passive"))
      (node (ref "MN30") (pin "2") (pinfunction "2_2") (pintype "passive"))
      (node (ref "MN32") (pin "2") (pinfunction "2_2") (pintype "passive"))
    )
    (net (code "38") (name "/TXRF2_2AB_P") (class "Default")
      (node (ref "IC1") (pin "A13") (pinfunction "pa2op_2_A13") (pintype "passive"))
      (node (ref "MN25") (pin "1") (pinfunction "1_1") (pintype "passive"))
      (node (ref "MN29") (pin "2") (pinfunction "2_2") (pintype "passive"))
      (node (ref "MN30") (pin "1") (pinfunction "1_1") (pintype "passive"))
    )
    (net (code "39") (name "/TXRF2_2BB_N") (class "Default")
      (node (ref "MN31") (pin "1") (pinfunction "1_1") (pintype "passive"))
      (node (ref "MN32") (pin "1") (pinfunction "1_1") (pintype "passive"))
      (node (ref "T4") (pin "4") (pinfunction "4_4") (pintype "passive"))
    )
    (net (code "40") (name "/TXRF2_2BB_P") (class "Default")
      (node (ref "MN29") (pin "1") (pinfunction "1_1") (pintype "passive"))
      (node (ref "MN31") (pin "2") (pinfunction "2_2") (pintype "passive"))
      (node (ref "T4") (pin "6") (pinfunction "6_6") (pintype "passive"))
    )
    (net (code "41") (name "GND") (class "Default")
      (node (ref "C10") (pin "1") (pinfunction "1_1") (pintype "passive"))
      (node (ref "C11") (pin "1") (pinfunction "1_1") (pintype "passive"))
      (node (ref "C12") (pin "1") (pinfunction "1_1") (pintype "passive"))
      (node (ref "C13") (pin "1") (pinfunction "1_1") (pintype "passive"))
      (node (ref "C4") (pin "1") (pinfunction "1_1") (pintype "passive"))
      (node (ref "C5") (pin "1") (pinfunction "1_1") (pintype "passive"))
      (node (ref "C6") (pin "1") (pinfunction "1_1") (pintype "passive"))
      (node (ref "C7") (pin "1") (pinfunction "1_1") (pintype "passive"))
      (node (ref "IC1") (pin "AJ7") (pinfunction "rfsn_l_RFE_2_AJ7") (pintype "passive"))
      (node (ref "IC1") (pin "AJ9") (pinfunction "rfsp_l_RFE_2_AJ9") (pintype "passive"))
      (node (ref "IC1") (pin "AK12") (pinfunction "rfsn_l_RFE_1_AK12") (pintype "passive"))
      (node (ref "IC1") (pin "AL13") (pinfunction "rfsp_l_RFE_1_AL13") (pintype "passive"))
      (node (ref "J1") (pin "2") (pinfunction "Y_2") (pintype "passive"))
      (node (ref "J10") (pin "2") (pinfunction "Y_2") (pintype "passive"))
      (node (ref "J2") (pin "2") (pinfunction "Y_2") (pintype "passive"))
      (node (ref "J3") (pin "2") (pinfunction "Y_2") (pintype "passive"))
      (node (ref "J4") (pin "2") (pinfunction "Y_2") (pintype "passive"))
      (node (ref "J5") (pin "2") (pinfunction "Y_2") (pintype "passive"))
      (node (ref "J6") (pin "2") (pinfunction "Y_2") (pintype "passive"))
      (node (ref "J7") (pin "2") (pinfunction "Y_2") (pintype "passive"))
      (node (ref "J8") (pin "2") (pinfunction "Y_2") (pintype "passive"))
      (node (ref "J9") (pin "2") (pinfunction "Y_2") (pintype "passive"))
      (node (ref "T1") (pin "2") (pinfunction "2_2") (pintype "passive"))
      (node (ref "T1") (pin "6") (pinfunction "6_6") (pintype "passive"))
      (node (ref "T10") (pin "2") (pinfunction "2_2") (pintype "passive"))
      (node (ref "T10") (pin "4") (pinfunction "4_4") (pintype "passive"))
      (node (ref "T2") (pin "2") (pinfunction "2_2") (pintype "passive"))
      (node (ref "T2") (pin "6") (pinfunction "6_6") (pintype "passive"))
      (node (ref "T3") (pin "3") (pinfunction "3_3") (pintype "passive"))
      (node (ref "T4") (pin "3") (pinfunction "3_3") (pintype "passive"))
      (node (ref "T5") (pin "2") (pinfunction "2_2") (pintype "passive"))
      (node (ref "T5") (pin "4") (pinfunction "4_4") (pintype "passive"))
      (node (ref "T6") (pin "2") (pinfunction "2_2") (pintype "passive"))
      (node (ref "T6") (pin "4") (pinfunction "4_4") (pintype "passive"))
      (node (ref "T7") (pin "2") (pinfunction "2_2") (pintype "passive"))
      (node (ref "T8") (pin "2") (pinfunction "2_2") (pintype "passive"))
      (node (ref "T9") (pin "2") (pinfunction "2_2") (pintype "passive"))
      (node (ref "T9") (pin "4") (pinfunction "4_4") (pintype "passive"))
    )
    (net (code "42") (name "Net-(C8-Pad2)") (class "Default")
      (node (ref "C8") (pin "2") (pinfunction "2_2") (pintype "passive"))
      (node (ref "T1") (pin "4") (pinfunction "4_4") (pintype "passive"))
    )
    (net (code "43") (name "Net-(C9-Pad2)") (class "Default")
      (node (ref "C9") (pin "2") (pinfunction "2_2") (pintype "passive"))
      (node (ref "T2") (pin "4") (pinfunction "4_4") (pintype "passive"))
    )
    (net (code "44") (name "Net-(C14-Pad2)") (class "Default")
      (node (ref "C14") (pin "2") (pinfunction "2_2") (pintype "passive"))
      (node (ref "T3") (pin "2") (pinfunction "2_2") (pintype "passive"))
    )
    (net (code "45") (name "Net-(C15-Pad2)") (class "Default")
      (node (ref "C15") (pin "2") (pinfunction "2_2") (pintype "passive"))
      (node (ref "T4") (pin "2") (pinfunction "2_2") (pintype "passive"))
    )
    (net (code "46") (name "Net-(C16-Pad2)") (class "Default")
      (node (ref "C16") (pin "2") (pinfunction "2_2") (pintype "passive"))
      (node (ref "T5") (pin "6") (pinfunction "6_6") (pintype "passive"))
    )
    (net (code "47") (name "Net-(C17-Pad2)") (class "Default")
      (node (ref "C17") (pin "2") (pinfunction "2_2") (pintype "passive"))
      (node (ref "T6") (pin "6") (pinfunction "6_6") (pintype "passive"))
    )
    (net (code "48") (name "Net-(C18-Pad2)") (class "Default")
      (node (ref "C18") (pin "2") (pinfunction "2_2") (pintype "passive"))
      (node (ref "T7") (pin "3") (pinfunction "3_3") (pintype "passive"))
    )
    (net (code "49") (name "Net-(C19-Pad2)") (class "Default")
      (node (ref "C19") (pin "2") (pinfunction "2_2") (pintype "passive"))
      (node (ref "T8") (pin "3") (pinfunction "3_3") (pintype "passive"))
    )
    (net (code "50") (name "Net-(C20-Pad2)") (class "Default")
      (node (ref "C20") (pin "2") (pinfunction "2_2") (pintype "passive"))
      (node (ref "T9") (pin "6") (pinfunction "6_6") (pintype "passive"))
    )
    (net (code "51") (name "Net-(C21-Pad2)") (class "Default")
      (node (ref "C21") (pin "2") (pinfunction "2_2") (pintype "passive"))
      (node (ref "T10") (pin "6") (pinfunction "6_6") (pintype "passive"))
    )
    (net (code "52") (name "Net-(J1-X)") (class "Default")
      (node (ref "C8") (pin "1") (pinfunction "1_1") (pintype "passive"))
      (node (ref "J1") (pin "1") (pinfunction "X_1") (pintype "passive"))
    )
    (net (code "53") (name "Net-(J2-X)") (class "Default")
      (node (ref "C9") (pin "1") (pinfunction "1_1") (pintype "passive"))
      (node (ref "J2") (pin "1") (pinfunction "X_1") (pintype "passive"))
    )
    (net (code "54") (name "Net-(J3-X)") (class "Default")
      (node (ref "C14") (pin "1") (pinfunction "1_1") (pintype "passive"))
      (node (ref "J3") (pin "1") (pinfunction "X_1") (pintype "passive"))
    )
    (net (code "55") (name "Net-(J4-X)") (class "Default")
      (node (ref "C15") (pin "1") (pinfunction "1_1") (pintype "passive"))
      (node (ref "J4") (pin "1") (pinfunction "X_1") (pintype "passive"))
    )
    (net (code "56") (name "Net-(J5-X)") (class "Default")
      (node (ref "C16") (pin "1") (pinfunction "1_1") (pintype "passive"))
      (node (ref "J5") (pin "1") (pinfunction "X_1") (pintype "passive"))
    )
    (net (code "57") (name "Net-(J6-X)") (class "Default")
      (node (ref "C17") (pin "1") (pinfunction "1_1") (pintype "passive"))
      (node (ref "J6") (pin "1") (pinfunction "X_1") (pintype "passive"))
    )
    (net (code "58") (name "Net-(J7-X)") (class "Default")
      (node (ref "C18") (pin "1") (pinfunction "1_1") (pintype "passive"))
      (node (ref "J7") (pin "1") (pinfunction "X_1") (pintype "passive"))
    )
    (net (code "59") (name "Net-(J8-X)") (class "Default")
      (node (ref "C19") (pin "1") (pinfunction "1_1") (pintype "passive"))
      (node (ref "J8") (pin "1") (pinfunction "X_1") (pintype "passive"))
    )
    (net (code "60") (name "Net-(J9-X)") (class "Default")
      (node (ref "C20") (pin "1") (pinfunction "1_1") (pintype "passive"))
      (node (ref "J9") (pin "1") (pinfunction "X_1") (pintype "passive"))
    )
    (net (code "61") (name "Net-(J10-X)") (class "Default")
      (node (ref "C21") (pin "1") (pinfunction "1_1") (pintype "passive"))
      (node (ref "J10") (pin "1") (pinfunction "X_1") (pintype "passive"))
    )
    (net (code "62") (name "Net-(MN1-Pad1)") (class "Default")
      (node (ref "MN1") (pin "1") (pinfunction "1_1") (pintype "passive"))
      (node (ref "MN5") (pin "2") (pinfunction "2_2") (pintype "passive"))
    )
    (net (code "63") (name "Net-(MN2-Pad1)") (class "Default")
      (node (ref "MN2") (pin "1") (pinfunction "1_1") (pintype "passive"))
      (node (ref "MN6") (pin "2") (pinfunction "2_2") (pintype "passive"))
    )
    (net (code "64") (name "Net-(MN3-Pad1)") (class "Default")
      (node (ref "MN3") (pin "1") (pinfunction "1_1") (pintype "passive"))
      (node (ref "MN7") (pin "2") (pinfunction "2_2") (pintype "passive"))
    )
    (net (code "65") (name "Net-(MN4-Pad1)") (class "Default")
      (node (ref "MN4") (pin "1") (pinfunction "1_1") (pintype "passive"))
      (node (ref "MN8") (pin "2") (pinfunction "2_2") (pintype "passive"))
    )
    (net (code "66") (name "Net-(MN17-Pad1)") (class "Default")
      (node (ref "MN17") (pin "1") (pinfunction "1_1") (pintype "passive"))
      (node (ref "MN21") (pin "2") (pinfunction "2_2") (pintype "passive"))
    )
    (net (code "67") (name "Net-(MN18-Pad1)") (class "Default")
      (node (ref "MN18") (pin "1") (pinfunction "1_1") (pintype "passive"))
      (node (ref "MN22") (pin "2") (pinfunction "2_2") (pintype "passive"))
    )
    (net (code "68") (name "Net-(MN19-Pad1)") (class "Default")
      (node (ref "MN19") (pin "1") (pinfunction "1_1") (pintype "passive"))
      (node (ref "MN24") (pin "2") (pinfunction "2_2") (pintype "passive"))
    )
    (net (code "69") (name "Net-(MN20-Pad1)") (class "Default")
      (node (ref "MN20") (pin "1") (pinfunction "1_1") (pintype "passive"))
      (node (ref "MN25") (pin "2") (pinfunction "2_2") (pintype "passive"))
    )
    (net (code "70") (name "VCC1P8_LMS") (class "Default")
      (node (ref "C10") (pin "2") (pinfunction "2_2") (pintype "passive"))
      (node (ref "C11") (pin "2") (pinfunction "2_2") (pintype "passive"))
      (node (ref "C12") (pin "2") (pinfunction "2_2") (pintype "passive"))
      (node (ref "C13") (pin "2") (pinfunction "2_2") (pintype "passive"))
      (node (ref "C4") (pin "2") (pinfunction "2_2") (pintype "passive"))
      (node (ref "C5") (pin "2") (pinfunction "2_2") (pintype "passive"))
      (node (ref "C6") (pin "2") (pinfunction "2_2") (pintype "passive"))
      (node (ref "C7") (pin "2") (pinfunction "2_2") (pintype "passive"))
      (node (ref "MN1") (pin "2") (pinfunction "2_2") (pintype "passive"))
      (node (ref "MN17") (pin "2") (pinfunction "2_2") (pintype "passive"))
      (node (ref "MN18") (pin "2") (pinfunction "2_2") (pintype "passive"))
      (node (ref "MN19") (pin "2") (pinfunction "2_2") (pintype "passive"))
      (node (ref "MN2") (pin "2") (pinfunction "2_2") (pintype "passive"))
      (node (ref "MN20") (pin "2") (pinfunction "2_2") (pintype "passive"))
      (node (ref "MN3") (pin "2") (pinfunction "2_2") (pintype "passive"))
      (node (ref "MN4") (pin "2") (pinfunction "2_2") (pintype "passive"))
    )
  )
)
